# untitled.net
KiCad netlist of a schematic drawn in EAGLE
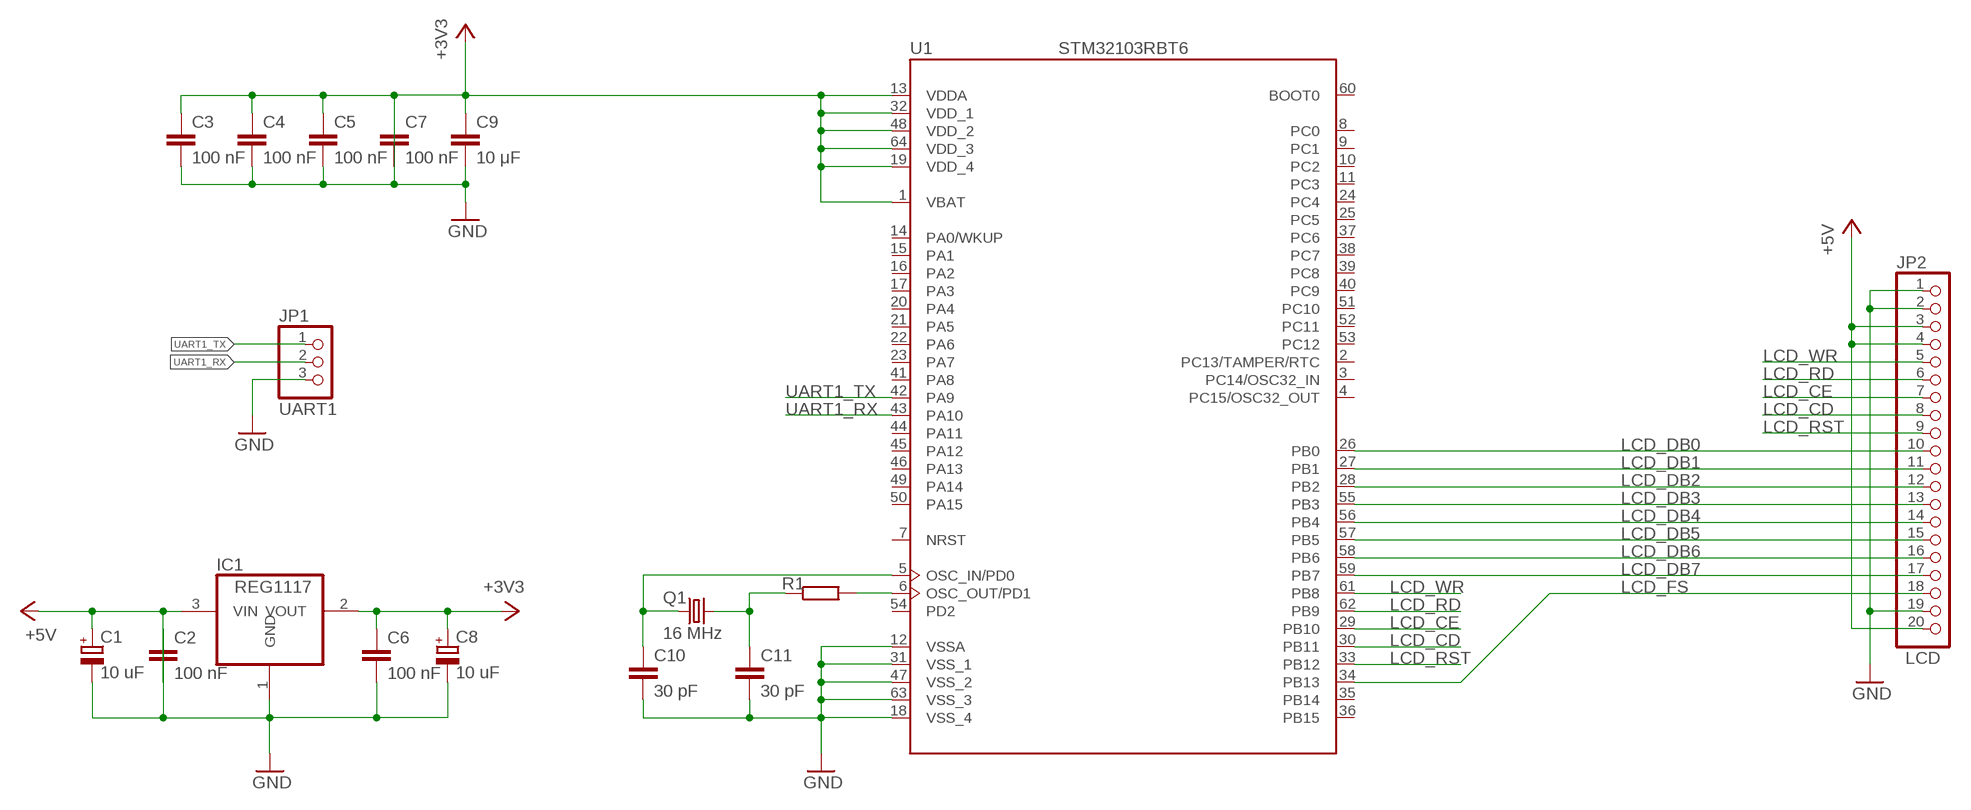
[diagram p0: schematic, sheet 1]

(export (version "E")
  (design (tool "Eeschema 10.0.6"))
  (components
    (comp (ref "C1")
      (value "10 uF")
      (footprint "eagle-import:A_3216-18W")
      (libsource (lib "eagle-import") (part "CPOL-EUA/3216-18W"))
    )
    (comp (ref "C2")
      (value "100 nF")
      (footprint "eagle-import:C1206")
      (libsource (lib "eagle-import") (part "C-EUC1206"))
    )
    (comp (ref "C3")
      (value "100 nF")
      (footprint "eagle-import:C1206")
      (libsource (lib "eagle-import") (part "C-EUC1206"))
    )
    (comp (ref "C4")
      (value "100 nF")
      (footprint "eagle-import:C1206")
      (libsource (lib "eagle-import") (part "C-EUC1206"))
    )
    (comp (ref "C5")
      (value "100 nF")
      (footprint "eagle-import:C1206")
      (libsource (lib "eagle-import") (part "C-EUC1206"))
    )
    (comp (ref "C6")
      (value "100 nF")
      (footprint "eagle-import:C1206")
      (libsource (lib "eagle-import") (part "C-EUC1206"))
    )
    (comp (ref "C7")
      (value "100 nF")
      (footprint "eagle-import:C1206")
      (libsource (lib "eagle-import") (part "C-EUC1206"))
    )
    (comp (ref "C8")
      (value "10 uF")
      (footprint "eagle-import:A_3216-18W")
      (libsource (lib "eagle-import") (part "CPOL-EUA/3216-18W"))
    )
    (comp (ref "C9")
      (value "10 μF")
      (footprint "eagle-import:C1206")
      (libsource (lib "eagle-import") (part "C-EUC1206"))
    )
    (comp (ref "C10")
      (value "30 pF")
      (footprint "eagle-import:C1206")
      (libsource (lib "eagle-import") (part "C-EUC1206"))
    )
    (comp (ref "C11")
      (value "30 pF")
      (footprint "eagle-import:C1206")
      (libsource (lib "eagle-import") (part "C-EUC1206"))
    )
    (comp (ref "IC1")
      (value "REG1117")
      (footprint "eagle-import:SOT223")
      (libsource (lib "eagle-import") (part "REG1117"))
    )
    (comp (ref "JP1")
      (value "PINHD-1X3")
      (footprint "eagle-import:1X03")
      (libsource (lib "eagle-import") (part "PINHD-1X3"))
    )
    (comp (ref "JP2")
      (value "PINHD-1X20")
      (footprint "eagle-import:1X20")
      (libsource (lib "eagle-import") (part "PINHD-1X20"))
    )
    (comp (ref "Q1")
      (value "16 MHz")
      (footprint "eagle-import:HC49_S")
      (libsource (lib "eagle-import") (part "CRYSTALHC49S"))
    )
    (comp (ref "R1")
      (value "R-EU_R1206")
      (footprint "eagle-import:R1206")
      (libsource (lib "eagle-import") (part "R-EU_R1206"))
    )
    (comp (ref "U1")
      (value "STM32103RBT6")
      (footprint "eagle-import:LQFP64")
      (libsource (lib "eagle-import") (part "STM32103RBT6"))
    )
  )
  (nets
    (net (code "1") (name "+3V3") (class "Default")
      (node (ref "C3") (pin "1") (pinfunction "1_1") (pintype "passive"))
      (node (ref "C4") (pin "1") (pinfunction "1_1") (pintype "passive"))
      (node (ref "C5") (pin "1") (pinfunction "1_1") (pintype "passive"))
      (node (ref "C6") (pin "1") (pinfunction "1_1") (pintype "passive"))
      (node (ref "C7") (pin "2") (pinfunction "2_2") (pintype "passive"))
      (node (ref "C8") (pin "+") (pinfunction "+_+") (pintype "passive"))
      (node (ref "C9") (pin "1") (pinfunction "1_1") (pintype "passive"))
      (node (ref "IC1") (pin "2") (pinfunction "VOUT_2") (pintype "output"))
      (node (ref "U1") (pin "1") (pinfunction "VBAT_1") (pintype "power_in"))
      (node (ref "U1") (pin "13") (pinfunction "VDDA_13") (pintype "power_in"))
      (node (ref "U1") (pin "19") (pinfunction "VDD_4_19") (pintype "power_in"))
      (node (ref "U1") (pin "32") (pinfunction "VDD_1_32") (pintype "power_in"))
      (node (ref "U1") (pin "48") (pinfunction "VDD_2_48") (pintype "power_in"))
      (node (ref "U1") (pin "64") (pinfunction "VDD_3_64") (pintype "power_in"))
    )
    (net (code "2") (name "+5V") (class "Default")
      (node (ref "C1") (pin "+") (pinfunction "+_+") (pintype "passive"))
      (node (ref "C2") (pin "2") (pinfunction "2_2") (pintype "passive"))
      (node (ref "IC1") (pin "3") (pinfunction "VIN_3") (pintype "input"))
      (node (ref "JP2") (pin "20") (pinfunction "20_20") (pintype "passive"))
      (node (ref "JP2") (pin "3") (pinfunction "3_3") (pintype "passive"))
      (node (ref "JP2") (pin "4") (pinfunction "4_4") (pintype "passive"))
    )
    (net (code "3") (name "/LCD_CD") (class "Default")
      (node (ref "JP2") (pin "8") (pinfunction "8_8") (pintype "passive"))
      (node (ref "U1") (pin "30") (pinfunction "PB11_30") (pintype "bidirectional"))
    )
    (net (code "4") (name "/LCD_CE") (class "Default")
      (node (ref "JP2") (pin "7") (pinfunction "7_7") (pintype "passive"))
      (node (ref "U1") (pin "29") (pinfunction "PB10_29") (pintype "bidirectional"))
    )
    (net (code "5") (name "/LCD_DB0") (class "Default")
      (node (ref "JP2") (pin "10") (pinfunction "10_10") (pintype "passive"))
      (node (ref "U1") (pin "26") (pinfunction "PB0_26") (pintype "bidirectional"))
    )
    (net (code "6") (name "/LCD_DB1") (class "Default")
      (node (ref "JP2") (pin "11") (pinfunction "11_11") (pintype "passive"))
      (node (ref "U1") (pin "27") (pinfunction "PB1_27") (pintype "bidirectional"))
    )
    (net (code "7") (name "/LCD_DB2") (class "Default")
      (node (ref "JP2") (pin "12") (pinfunction "12_12") (pintype "passive"))
      (node (ref "U1") (pin "28") (pinfunction "PB2_28") (pintype "bidirectional"))
    )
    (net (code "8") (name "/LCD_DB3") (class "Default")
      (node (ref "JP2") (pin "13") (pinfunction "13_13") (pintype "passive"))
      (node (ref "U1") (pin "55") (pinfunction "PB3_55") (pintype "bidirectional"))
    )
    (net (code "9") (name "/LCD_DB4") (class "Default")
      (node (ref "JP2") (pin "14") (pinfunction "14_14") (pintype "passive"))
      (node (ref "U1") (pin "56") (pinfunction "PB4_56") (pintype "bidirectional"))
    )
    (net (code "10") (name "/LCD_DB5") (class "Default")
      (node (ref "JP2") (pin "15") (pinfunction "15_15") (pintype "passive"))
      (node (ref "U1") (pin "57") (pinfunction "PB5_57") (pintype "bidirectional"))
    )
    (net (code "11") (name "/LCD_DB6") (class "Default")
      (node (ref "JP2") (pin "16") (pinfunction "16_16") (pintype "passive"))
      (node (ref "U1") (pin "58") (pinfunction "PB6_58") (pintype "bidirectional"))
    )
    (net (code "12") (name "/LCD_DB7") (class "Default")
      (node (ref "JP2") (pin "17") (pinfunction "17_17") (pintype "passive"))
      (node (ref "U1") (pin "59") (pinfunction "PB7_59") (pintype "bidirectional"))
    )
    (net (code "13") (name "/LCD_FS") (class "Default")
      (node (ref "JP2") (pin "18") (pinfunction "18_18") (pintype "passive"))
      (node (ref "U1") (pin "34") (pinfunction "PB13_34") (pintype "bidirectional"))
    )
    (net (code "14") (name "/LCD_RD") (class "Default")
      (node (ref "JP2") (pin "6") (pinfunction "6_6") (pintype "passive"))
      (node (ref "U1") (pin "62") (pinfunction "PB9_62") (pintype "bidirectional"))
    )
    (net (code "15") (name "/LCD_RST") (class "Default")
      (node (ref "JP2") (pin "9") (pinfunction "9_9") (pintype "passive"))
      (node (ref "U1") (pin "33") (pinfunction "PB12_33") (pintype "bidirectional"))
    )
    (net (code "16") (name "/LCD_WR") (class "Default")
      (node (ref "JP2") (pin "5") (pinfunction "5_5") (pintype "passive"))
      (node (ref "U1") (pin "61") (pinfunction "PB8_61") (pintype "bidirectional"))
    )
    (net (code "17") (name "GND") (class "Default")
      (node (ref "C1") (pin "-") (pinfunction "-_-") (pintype "passive"))
      (node (ref "C10") (pin "2") (pinfunction "2_2") (pintype "passive"))
      (node (ref "C11") (pin "2") (pinfunction "2_2") (pintype "passive"))
      (node (ref "C2") (pin "1") (pinfunction "1_1") (pintype "passive"))
      (node (ref "C3") (pin "2") (pinfunction "2_2") (pintype "passive"))
      (node (ref "C4") (pin "2") (pinfunction "2_2") (pintype "passive"))
      (node (ref "C5") (pin "2") (pinfunction "2_2") (pintype "passive"))
      (node (ref "C6") (pin "2") (pinfunction "2_2") (pintype "passive"))
      (node (ref "C7") (pin "1") (pinfunction "1_1") (pintype "passive"))
      (node (ref "C8") (pin "-") (pinfunction "-_-") (pintype "passive"))
      (node (ref "C9") (pin "2") (pinfunction "2_2") (pintype "passive"))
      (node (ref "IC1") (pin "1") (pinfunction "GND_1") (pintype "power_in"))
      (node (ref "JP1") (pin "3") (pinfunction "3_3") (pintype "passive"))
      (node (ref "JP2") (pin "1") (pinfunction "1_1") (pintype "passive"))
      (node (ref "JP2") (pin "19") (pinfunction "19_19") (pintype "passive"))
      (node (ref "JP2") (pin "2") (pinfunction "2_2") (pintype "passive"))
      (node (ref "U1") (pin "12") (pinfunction "VSSA_12") (pintype "power_in"))
      (node (ref "U1") (pin "18") (pinfunction "VSS_4_18") (pintype "power_in"))
      (node (ref "U1") (pin "31") (pinfunction "VSS_1_31") (pintype "power_in"))
      (node (ref "U1") (pin "47") (pinfunction "VSS_2_47") (pintype "power_in"))
      (node (ref "U1") (pin "63") (pinfunction "VSS_3_63") (pintype "power_in"))
    )
    (net (code "18") (name "Net-(C11-Pad1)") (class "Default")
      (node (ref "C11") (pin "1") (pinfunction "1_1") (pintype "passive"))
      (node (ref "Q1") (pin "2") (pinfunction "2_2") (pintype "passive"))
      (node (ref "R1") (pin "1") (pinfunction "1_1") (pintype "passive"))
    )
    (net (code "19") (name "Net-(U1-OSC_IN{slash}PD0)") (class "Default")
      (node (ref "C10") (pin "1") (pinfunction "1_1") (pintype "passive"))
      (node (ref "Q1") (pin "1") (pinfunction "1_1") (pintype "passive"))
      (node (ref "U1") (pin "5") (pinfunction "OSC_IN/PD0_5") (pintype "input"))
    )
    (net (code "20") (name "Net-(U1-OSC_OUT{slash}PD1)") (class "Default")
      (node (ref "R1") (pin "2") (pinfunction "2_2") (pintype "passive"))
      (node (ref "U1") (pin "6") (pinfunction "OSC_OUT/PD1_6") (pintype "output"))
    )
    (net (code "21") (name "UART1_RX") (class "Default")
      (node (ref "JP1") (pin "2") (pinfunction "2_2") (pintype "passive"))
      (node (ref "U1") (pin "43") (pinfunction "PA10_43") (pintype "bidirectional"))
    )
    (net (code "22") (name "UART1_TX") (class "Default")
      (node (ref "JP1") (pin "1") (pinfunction "1_1") (pintype "passive"))
      (node (ref "U1") (pin "42") (pinfunction "PA9_42") (pintype "bidirectional"))
    )
    (net (code "23") (name "unconnected-(U1-BOOT0-Pad60)") (class "Default")
      (node (ref "U1") (pin "60") (pinfunction "BOOT0_60") (pintype "input"))
    )
    (net (code "24") (name "unconnected-(U1-NRST-Pad7)") (class "Default")
      (node (ref "U1") (pin "7") (pinfunction "NRST_7") (pintype "bidirectional"))
    )
    (net (code "25") (name "unconnected-(U1-PA0{slash}WKUP-Pad14)") (class "Default")
      (node (ref "U1") (pin "14") (pinfunction "PA0/WKUP_14") (pintype "bidirectional"))
    )
    (net (code "26") (name "unconnected-(U1-PA1-Pad15)") (class "Default")
      (node (ref "U1") (pin "15") (pinfunction "PA1_15") (pintype "bidirectional"))
    )
    (net (code "27") (name "unconnected-(U1-PA2-Pad16)") (class "Default")
      (node (ref "U1") (pin "16") (pinfunction "PA2_16") (pintype "bidirectional"))
    )
    (net (code "28") (name "unconnected-(U1-PA3-Pad17)") (class "Default")
      (node (ref "U1") (pin "17") (pinfunction "PA3_17") (pintype "bidirectional"))
    )
    (net (code "29") (name "unconnected-(U1-PA4-Pad20)") (class "Default")
      (node (ref "U1") (pin "20") (pinfunction "PA4_20") (pintype "bidirectional"))
    )
    (net (code "30") (name "unconnected-(U1-PA5-Pad21)") (class "Default")
      (node (ref "U1") (pin "21") (pinfunction "PA5_21") (pintype "bidirectional"))
    )
    (net (code "31") (name "unconnected-(U1-PA6-Pad22)") (class "Default")
      (node (ref "U1") (pin "22") (pinfunction "PA6_22") (pintype "bidirectional"))
    )
    (net (code "32") (name "unconnected-(U1-PA7-Pad23)") (class "Default")
      (node (ref "U1") (pin "23") (pinfunction "PA7_23") (pintype "bidirectional"))
    )
    (net (code "33") (name "unconnected-(U1-PA8-Pad41)") (class "Default")
      (node (ref "U1") (pin "41") (pinfunction "PA8_41") (pintype "bidirectional"))
    )
    (net (code "34") (name "unconnected-(U1-PA11-Pad44)") (class "Default")
      (node (ref "U1") (pin "44") (pinfunction "PA11_44") (pintype "bidirectional"))
    )
    (net (code "35") (name "unconnected-(U1-PA12-Pad45)") (class "Default")
      (node (ref "U1") (pin "45") (pinfunction "PA12_45") (pintype "bidirectional"))
    )
    (net (code "36") (name "unconnected-(U1-PA13-Pad46)") (class "Default")
      (node (ref "U1") (pin "46") (pinfunction "PA13_46") (pintype "bidirectional"))
    )
    (net (code "37") (name "unconnected-(U1-PA14-Pad49)") (class "Default")
      (node (ref "U1") (pin "49") (pinfunction "PA14_49") (pintype "bidirectional"))
    )
    (net (code "38") (name "unconnected-(U1-PA15-Pad50)") (class "Default")
      (node (ref "U1") (pin "50") (pinfunction "PA15_50") (pintype "bidirectional"))
    )
    (net (code "39") (name "unconnected-(U1-PB14-Pad35)") (class "Default")
      (node (ref "U1") (pin "35") (pinfunction "PB14_35") (pintype "bidirectional"))
    )
    (net (code "40") (name "unconnected-(U1-PB15-Pad36)") (class "Default")
      (node (ref "U1") (pin "36") (pinfunction "PB15_36") (pintype "bidirectional"))
    )
    (net (code "41") (name "unconnected-(U1-PC0-Pad8)") (class "Default")
      (node (ref "U1") (pin "8") (pinfunction "PC0_8") (pintype "bidirectional"))
    )
    (net (code "42") (name "unconnected-(U1-PC1-Pad9)") (class "Default")
      (node (ref "U1") (pin "9") (pinfunction "PC1_9") (pintype "bidirectional"))
    )
    (net (code "43") (name "unconnected-(U1-PC2-Pad10)") (class "Default")
      (node (ref "U1") (pin "10") (pinfunction "PC2_10") (pintype "bidirectional"))
    )
    (net (code "44") (name "unconnected-(U1-PC3-Pad11)") (class "Default")
      (node (ref "U1") (pin "11") (pinfunction "PC3_11") (pintype "bidirectional"))
    )
    (net (code "45") (name "unconnected-(U1-PC4-Pad24)") (class "Default")
      (node (ref "U1") (pin "24") (pinfunction "PC4_24") (pintype "bidirectional"))
    )
    (net (code "46") (name "unconnected-(U1-PC5-Pad25)") (class "Default")
      (node (ref "U1") (pin "25") (pinfunction "PC5_25") (pintype "bidirectional"))
    )
    (net (code "47") (name "unconnected-(U1-PC6-Pad37)") (class "Default")
      (node (ref "U1") (pin "37") (pinfunction "PC6_37") (pintype "bidirectional"))
    )
    (net (code "48") (name "unconnected-(U1-PC7-Pad38)") (class "Default")
      (node (ref "U1") (pin "38") (pinfunction "PC7_38") (pintype "bidirectional"))
    )
    (net (code "49") (name "unconnected-(U1-PC8-Pad39)") (class "Default")
      (node (ref "U1") (pin "39") (pinfunction "PC8_39") (pintype "bidirectional"))
    )
    (net (code "50") (name "unconnected-(U1-PC9-Pad40)") (class "Default")
      (node (ref "U1") (pin "40") (pinfunction "PC9_40") (pintype "bidirectional"))
    )
    (net (code "51") (name "unconnected-(U1-PC10-Pad51)") (class "Default")
      (node (ref "U1") (pin "51") (pinfunction "PC10_51") (pintype "bidirectional"))
    )
    (net (code "52") (name "unconnected-(U1-PC11-Pad52)") (class "Default")
      (node (ref "U1") (pin "52") (pinfunction "PC11_52") (pintype "bidirectional"))
    )
    (net (code "53") (name "unconnected-(U1-PC12-Pad53)") (class "Default")
      (node (ref "U1") (pin "53") (pinfunction "PC12_53") (pintype "bidirectional"))
    )
    (net (code "54") (name "unconnected-(U1-PC13{slash}TAMPER{slash}RTC-Pad2)") (class "Default")
      (node (ref "U1") (pin "2") (pinfunction "PC13/TAMPER/RTC_2") (pintype "bidirectional"))
    )
    (net (code "55") (name "unconnected-(U1-PC14{slash}OSC32_IN-Pad3)") (class "Default")
      (node (ref "U1") (pin "3") (pinfunction "PC14/OSC32_IN_3") (pintype "bidirectional"))
    )
    (net (code "56") (name "unconnected-(U1-PC15{slash}OSC32_OUT-Pad4)") (class "Default")
      (node (ref "U1") (pin "4") (pinfunction "PC15/OSC32_OUT_4") (pintype "bidirectional"))
    )
    (net (code "57") (name "unconnected-(U1-PD2-Pad54)") (class "Default")
      (node (ref "U1") (pin "54") (pinfunction "PD2_54") (pintype "bidirectional"))
    )
  )
)
